# final_version.net
KiCad netlist of a schematic drawn in EAGLE
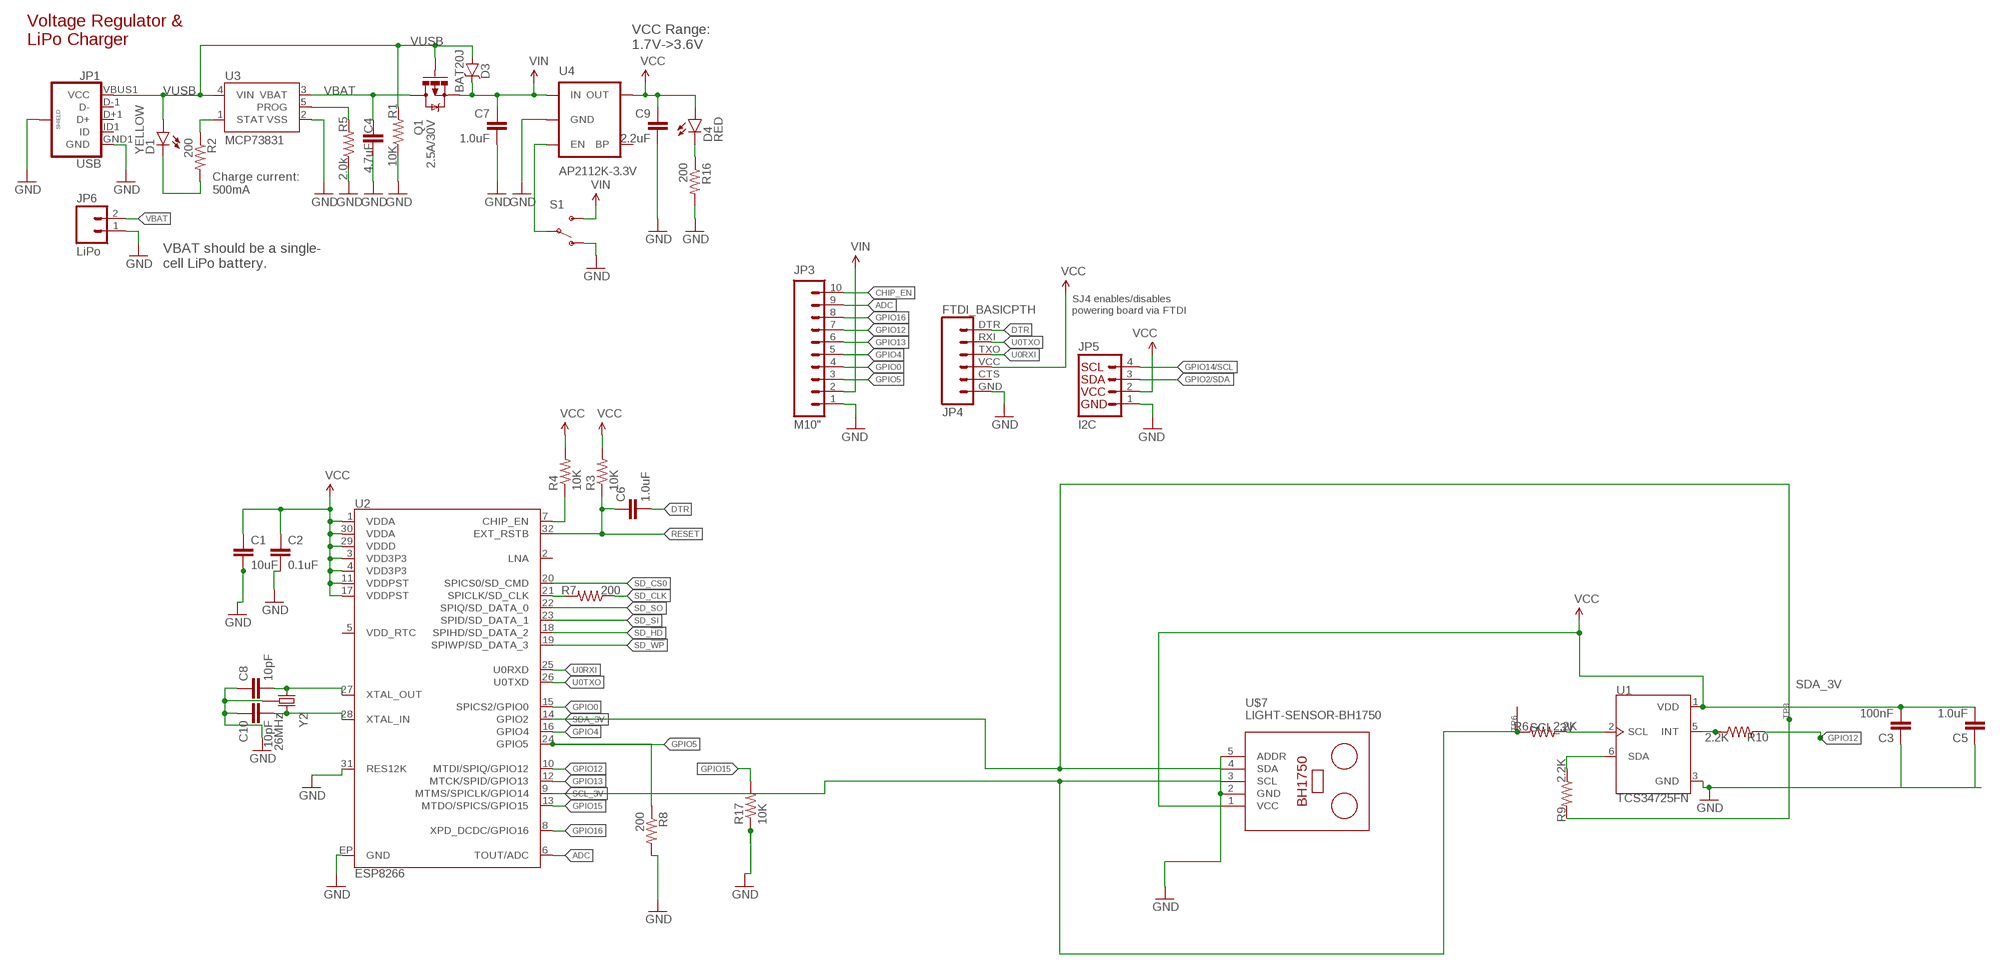
[diagram p0: schematic, sheet 1]

(export (version "E")
  (design (tool "Eeschema 10.0.6"))
  (components
    (comp (ref "C1")
      (value "10uF")
      (footprint "eagle-import:0603-CAP")
      (libsource (lib "eagle-import") (part "10UF-6.3V-20%(0603)"))
    )
    (comp (ref "C2")
      (value "0.1uF")
      (footprint "eagle-import:0603-CAP")
      (libsource (lib "eagle-import") (part "0.1UF-25V(+80/-20%)(0603)"))
    )
    (comp (ref "C3")
      (value "100nF")
      (footprint "eagle-import:0603-CAP")
      (libsource (lib "eagle-import") (part "1.0UF-16V-10%(0603)"))
    )
    (comp (ref "C4")
      (value "4.7uF")
      (footprint "eagle-import:0603-CAP")
      (libsource (lib "eagle-import") (part "4.7UF-6.3V-10%(0603)0603"))
    )
    (comp (ref "C5")
      (value "1.0uF")
      (footprint "eagle-import:0603-CAP")
      (libsource (lib "eagle-import") (part "1.0UF-16V-10%(0603)"))
    )
    (comp (ref "C6")
      (value "1.0uF")
      (footprint "eagle-import:0603-CAP")
      (libsource (lib "eagle-import") (part "1.0UF-16V-10%(0603)"))
    )
    (comp (ref "C7")
      (value "1.0uF")
      (footprint "eagle-import:0805")
      (libsource (lib "eagle-import") (part "1.0UF-25V-+80/-20(0805)"))
    )
    (comp (ref "C8")
      (value "10pF")
      (footprint "eagle-import:0603-CAP")
      (libsource (lib "eagle-import") (part "10PF-50V-5%(0603)"))
    )
    (comp (ref "C9")
      (value "2.2uF")
      (footprint "eagle-import:0603-CAP")
      (libsource (lib "eagle-import") (part "2.2UF-10V-20%(0603)"))
    )
    (comp (ref "C10")
      (value "10pF")
      (footprint "eagle-import:0603-CAP")
      (libsource (lib "eagle-import") (part "10PF-50V-5%(0603)"))
    )
    (comp (ref "D1")
      (value "YELLOW")
      (footprint "eagle-import:LED-0603")
      (libsource (lib "eagle-import") (part "LED-YELLOW0603"))
    )
    (comp (ref "D3")
      (value "BAT20J")
      (footprint "eagle-import:SOD-323")
      (libsource (lib "eagle-import") (part "DIODE-SCHOTTKY-BAT20J"))
    )
    (comp (ref "D4")
      (value "RED")
      (footprint "eagle-import:LED-0603")
      (libsource (lib "eagle-import") (part "LED-RED0603"))
    )
    (comp (ref "JP1")
      (value "USB")
      (footprint "eagle-import:USB-B-MICRO-SMD_V03")
      (libsource (lib "eagle-import") (part "USB_MICROB_PLUGCONN-11752"))
    )
    (comp (ref "JP3")
      (value "M10\"")
      (footprint "eagle-import:1X10")
      (libsource (lib "eagle-import") (part "M10{dblquote}"))
    )
    (comp (ref "JP4")
      (value "FTDI_BASICPTH")
      (footprint "eagle-import:FTDI_BASIC")
      (libsource (lib "eagle-import") (part "FTDI_BASICPTH"))
    )
    (comp (ref "JP5")
      (value "I2C")
      (footprint "eagle-import:1X04")
      (libsource (lib "eagle-import") (part "I2C_STANDARD"))
    )
    (comp (ref "JP6")
      (value "LiPo")
      (footprint "eagle-import:JST-2-PTH")
      (libsource (lib "eagle-import") (part "M02JST-PTH-2"))
    )
    (comp (ref "Q1")
      (value "2.5A/30V")
      (footprint "eagle-import:SOT23-3")
      (libsource (lib "eagle-import") (part "MOSFET-PCHANNELDMG2307L"))
    )
    (comp (ref "R1")
      (value "10K")
      (footprint "eagle-import:0603-RES")
      (libsource (lib "eagle-import") (part "10KOHM1/10W1%(0603)0603"))
    )
    (comp (ref "R2")
      (value "200")
      (footprint "eagle-import:0603-RES")
      (libsource (lib "eagle-import") (part "200OHM1/10W1%(0603)"))
    )
    (comp (ref "R3")
      (value "10K")
      (footprint "eagle-import:0603-RES")
      (libsource (lib "eagle-import") (part "10KOHM1/10W1%(0603)0603"))
    )
    (comp (ref "R4")
      (value "10K")
      (footprint "eagle-import:0603-RES")
      (libsource (lib "eagle-import") (part "10KOHM1/10W1%(0603)0603"))
    )
    (comp (ref "R5")
      (value "2.0k")
      (footprint "eagle-import:0603-RES")
      (libsource (lib "eagle-import") (part "2.0KOHM1/10W5%(0603)"))
    )
    (comp (ref "R6")
      (value "2.2K")
      (footprint "eagle-import:0603-RES")
      (libsource (lib "eagle-import") (part "200OHM1/10W1%(0603)"))
    )
    (comp (ref "R7")
      (value "200")
      (footprint "eagle-import:0603-RES")
      (libsource (lib "eagle-import") (part "200OHM1/10W1%(0603)"))
    )
    (comp (ref "R8")
      (value "200")
      (footprint "eagle-import:0603-RES")
      (libsource (lib "eagle-import") (part "200OHM1/10W1%(0603)"))
    )
    (comp (ref "R9")
      (value "2.2K")
      (footprint "eagle-import:0603-RES")
      (libsource (lib "eagle-import") (part "200OHM1/10W1%(0603)"))
    )
    (comp (ref "R10")
      (value "2.2K")
      (footprint "eagle-import:0603-RES")
      (libsource (lib "eagle-import") (part "200OHM1/10W1%(0603)"))
    )
    (comp (ref "R16")
      (value "200")
      (footprint "eagle-import:0603-RES")
      (libsource (lib "eagle-import") (part "200OHM1/10W1%(0603)"))
    )
    (comp (ref "R17")
      (value "10K")
      (footprint "eagle-import:0603-RES")
      (libsource (lib "eagle-import") (part "10KOHM1/10W1%(0603)0603"))
    )
    (comp (ref "S1")
      (value "SWITCH-SPDT-SMD-A")
      (footprint "eagle-import:SWITCH-SPST-SMD-A")
      (libsource (lib "eagle-import") (part "SWITCH-SPDT-SMD-A"))
    )
    (comp (ref "TP3")
      (value "SEWTAP0.5IN")
      (footprint "eagle-import:SEWINGTAP_0.5")
      (libsource (lib "eagle-import") (part "SEWTAP0.5IN"))
    )
    (comp (ref "TP6")
      (value "SEWTAP0.5IN")
      (footprint "eagle-import:SEWINGTAP_0.5")
      (libsource (lib "eagle-import") (part "SEWTAP0.5IN"))
    )
    (comp (ref "U$7")
      (value "LIGHT-SENSOR-BH1750")
      (footprint "eagle-import:LIGHT-SENSOR-BH1750")
      (libsource (lib "eagle-import") (part "LIGHT-SENSOR-BH1750"))
    )
    (comp (ref "U1")
      (value "TCS34725FN")
      (footprint "eagle-import:SON65P200X240X70-6N")
      (fields (field (name "DIGI-KEY_PART_NUMBER") "TCS34725FNCT-ND") (field (name "MF") "ams"))
      (libsource (lib "eagle-import") (part "TCS34725FN"))
    )
    (comp (ref "U2")
      (value "ESP8266")
      (footprint "eagle-import:QFN32")
      (libsource (lib "eagle-import") (part "ESP8266"))
    )
    (comp (ref "U3")
      (value "MCP73831")
      (footprint "eagle-import:SOT23-5")
      (libsource (lib "eagle-import") (part "MCP73831"))
    )
    (comp (ref "U4")
      (value "AP2112K-3.3V")
      (footprint "eagle-import:SOT23-5")
      (libsource (lib "eagle-import") (part "V_REG_LDOSMD"))
    )
    (comp (ref "Y2")
      (value "26MHz")
      (footprint "eagle-import:CRYSTAL-SMD-3.2X2.5")
      (libsource (lib "eagle-import") (part "CRYSTAL-GROUNDED3.2X2.5"))
    )
  )
  (nets
    (net (code "1") (name "/SD_~{HD}") (class "Default")
      (node (ref "U2") (pin "18") (pinfunction "SPIHD/SD_DATA_2_18") (pintype "bidirectional"))
    )
    (net (code "2") (name "/SD_~{WP}") (class "Default")
      (node (ref "U2") (pin "19") (pinfunction "SPIWP/SD_DATA_3_19") (pintype "bidirectional"))
    )
    (net (code "3") (name "/VUSB") (class "Default")
      (node (ref "D1") (pin "A") (pinfunction "A_A") (pintype "passive"))
      (node (ref "D3") (pin "A") (pinfunction "A_A") (pintype "passive"))
      (node (ref "JP1") (pin "VBUS1") (pinfunction "VCC_VBUS1") (pintype "bidirectional"))
      (node (ref "Q1") (pin "1") (pinfunction "G_1") (pintype "passive"))
      (node (ref "R1") (pin "2") (pinfunction "2_2") (pintype "passive"))
      (node (ref "U3") (pin "4") (pinfunction "VIN_4") (pintype "power_in"))
    )
    (net (code "4") (name "ADC") (class "Default")
      (node (ref "JP3") (pin "9") (pinfunction "9_9") (pintype "passive"))
      (node (ref "U2") (pin "6") (pinfunction "TOUT/ADC_6") (pintype "bidirectional"))
    )
    (net (code "5") (name "CHIP_EN") (class "Default")
      (node (ref "JP3") (pin "10") (pinfunction "10_10") (pintype "passive"))
      (node (ref "R4") (pin "1") (pinfunction "1_1") (pintype "passive"))
      (node (ref "U2") (pin "7") (pinfunction "CHIP_EN_7") (pintype "bidirectional"))
    )
    (net (code "6") (name "DTR") (class "Default")
      (node (ref "C6") (pin "2") (pinfunction "2_2") (pintype "passive"))
      (node (ref "JP4") (pin "DTR") (pinfunction "1_DTR") (pintype "passive"))
    )
    (net (code "7") (name "GND") (class "Default")
      (node (ref "C1") (pin "2") (pinfunction "2_2") (pintype "passive"))
      (node (ref "C10") (pin "1") (pinfunction "1_1") (pintype "passive"))
      (node (ref "C2") (pin "2") (pinfunction "2_2") (pintype "passive"))
      (node (ref "C3") (pin "1") (pinfunction "1_1") (pintype "passive"))
      (node (ref "C4") (pin "2") (pinfunction "2_2") (pintype "passive"))
      (node (ref "C5") (pin "1") (pinfunction "1_1") (pintype "passive"))
      (node (ref "C7") (pin "2") (pinfunction "2_2") (pintype "passive"))
      (node (ref "C8") (pin "1") (pinfunction "1_1") (pintype "passive"))
      (node (ref "C9") (pin "2") (pinfunction "2_2") (pintype "passive"))
      (node (ref "JP1") (pin "GND1") (pinfunction "GND_GND1") (pintype "bidirectional"))
      (node (ref "JP1") (pin "SHIELD1") (pinfunction "SHIELD_SHIELD1") (pintype "bidirectional"))
      (node (ref "JP1") (pin "SHIELD2") (pinfunction "SHIELD_SHIELD2") (pintype "bidirectional"))
      (node (ref "JP1") (pin "SHIELD3") (pinfunction "SHIELD_SHIELD3") (pintype "bidirectional"))
      (node (ref "JP3") (pin "1") (pinfunction "1_1") (pintype "passive"))
      (node (ref "JP4") (pin "GND") (pinfunction "6_GND") (pintype "passive"))
      (node (ref "JP5") (pin "1") (pinfunction "1_1") (pintype "passive"))
      (node (ref "JP6") (pin "1") (pinfunction "1_1") (pintype "passive"))
      (node (ref "R1") (pin "1") (pinfunction "1_1") (pintype "passive"))
      (node (ref "R16") (pin "2") (pinfunction "2_2") (pintype "passive"))
      (node (ref "R17") (pin "1") (pinfunction "1_1") (pintype "passive"))
      (node (ref "R5") (pin "1") (pinfunction "1_1") (pintype "passive"))
      (node (ref "R8") (pin "2") (pinfunction "2_2") (pintype "passive"))
      (node (ref "S1") (pin "1") (pinfunction "O_1") (pintype "passive"))
      (node (ref "U$7") (pin "2") (pinfunction "GND_2") (pintype "power_in"))
      (node (ref "U$7") (pin "5") (pinfunction "ADDR_5") (pintype "bidirectional"))
      (node (ref "U1") (pin "3") (pinfunction "GND_3") (pintype "power_in"))
      (node (ref "U2") (pin "31") (pinfunction "RES12K_31") (pintype "bidirectional"))
      (node (ref "U2") (pin "EP") (pinfunction "GND_EP") (pintype "bidirectional"))
      (node (ref "U3") (pin "2") (pinfunction "VSS_2") (pintype "power_in"))
      (node (ref "U4") (pin "2") (pinfunction "GND_2") (pintype "input"))
      (node (ref "Y2") (pin "2") (pinfunction "GND_2") (pintype "passive"))
      (node (ref "Y2") (pin "4") (pinfunction "GND_4") (pintype "passive"))
    )
    (net (code "8") (name "GPIO0") (class "Default")
      (node (ref "JP3") (pin "4") (pinfunction "4_4") (pintype "passive"))
      (node (ref "U2") (pin "15") (pinfunction "SPICS2/GPIO0_15") (pintype "bidirectional"))
    )
    (net (code "9") (name "GPIO2{slash}SDA") (class "Default")
      (node (ref "JP5") (pin "3") (pinfunction "3_3") (pintype "passive"))
    )
    (net (code "10") (name "GPIO4") (class "Default")
      (node (ref "JP3") (pin "5") (pinfunction "5_5") (pintype "passive"))
      (node (ref "U2") (pin "16") (pinfunction "GPIO4_16") (pintype "bidirectional"))
    )
    (net (code "11") (name "GPIO5") (class "Default")
      (node (ref "JP3") (pin "3") (pinfunction "3_3") (pintype "passive"))
      (node (ref "R8") (pin "1") (pinfunction "1_1") (pintype "passive"))
      (node (ref "U2") (pin "24") (pinfunction "GPIO5_24") (pintype "bidirectional"))
    )
    (net (code "12") (name "GPIO12") (class "Default")
      (node (ref "JP3") (pin "7") (pinfunction "7_7") (pintype "passive"))
      (node (ref "U2") (pin "10") (pinfunction "MTDI/SPIQ/GPIO12_10") (pintype "bidirectional"))
    )
    (net (code "13") (name "GPIO13") (class "Default")
      (node (ref "JP3") (pin "6") (pinfunction "6_6") (pintype "passive"))
      (node (ref "U2") (pin "12") (pinfunction "MTCK/SPID/GPIO13_12") (pintype "bidirectional"))
    )
    (net (code "14") (name "GPIO14{slash}SCL") (class "Default")
      (node (ref "JP5") (pin "4") (pinfunction "4_4") (pintype "passive"))
    )
    (net (code "15") (name "GPIO15") (class "Default")
      (node (ref "R17") (pin "2") (pinfunction "2_2") (pintype "passive"))
      (node (ref "U2") (pin "13") (pinfunction "MTDO/SPICS/GPIO15_13") (pintype "bidirectional"))
    )
    (net (code "16") (name "GPIO16") (class "Default")
      (node (ref "JP3") (pin "8") (pinfunction "8_8") (pintype "passive"))
      (node (ref "U2") (pin "8") (pinfunction "XPD_DCDC/GPIO16_8") (pintype "bidirectional"))
    )
    (net (code "17") (name "Net-(D1-PadC)") (class "Default")
      (node (ref "D1") (pin "C") (pinfunction "C_C") (pintype "passive"))
      (node (ref "R2") (pin "2") (pinfunction "2_2") (pintype "passive"))
    )
    (net (code "18") (name "Net-(D4-PadC)") (class "Default")
      (node (ref "D4") (pin "C") (pinfunction "C_C") (pintype "passive"))
      (node (ref "R16") (pin "1") (pinfunction "1_1") (pintype "passive"))
    )
    (net (code "19") (name "Net-(S1-P)") (class "Default")
      (node (ref "S1") (pin "2") (pinfunction "P_2") (pintype "passive"))
      (node (ref "U4") (pin "3") (pinfunction "EN_3") (pintype "input"))
    )
    (net (code "20") (name "Net-(U1-INT)") (class "Default")
      (node (ref "R10") (pin "1") (pinfunction "1_1") (pintype "passive"))
      (node (ref "U1") (pin "5") (pinfunction "INT_5") (pintype "output"))
    )
    (net (code "21") (name "Net-(U1-SCL)") (class "Default")
      (node (ref "R6") (pin "1") (pinfunction "1_1") (pintype "passive"))
      (node (ref "U1") (pin "2") (pinfunction "SCL_2") (pintype "input"))
    )
    (net (code "22") (name "Net-(U1-SDA)") (class "Default")
      (node (ref "R9") (pin "1") (pinfunction "1_1") (pintype "passive"))
      (node (ref "U1") (pin "6") (pinfunction "SDA_6") (pintype "bidirectional"))
    )
    (net (code "23") (name "Net-(U2-SPICLK{slash}SD_CLK)") (class "Default")
      (node (ref "R7") (pin "2") (pinfunction "2_2") (pintype "passive"))
      (node (ref "U2") (pin "21") (pinfunction "SPICLK/SD_CLK_21") (pintype "bidirectional"))
    )
    (net (code "24") (name "Net-(U2-XTAL_IN)") (class "Default")
      (node (ref "C10") (pin "2") (pinfunction "2_2") (pintype "passive"))
      (node (ref "U2") (pin "28") (pinfunction "XTAL_IN_28") (pintype "bidirectional"))
      (node (ref "Y2") (pin "3") (pinfunction "2_3") (pintype "passive"))
    )
    (net (code "25") (name "Net-(U2-XTAL_OUT)") (class "Default")
      (node (ref "C8") (pin "2") (pinfunction "2_2") (pintype "passive"))
      (node (ref "U2") (pin "27") (pinfunction "XTAL_OUT_27") (pintype "bidirectional"))
      (node (ref "Y2") (pin "1") (pinfunction "1_1") (pintype "passive"))
    )
    (net (code "26") (name "Net-(U3-PROG)") (class "Default")
      (node (ref "R5") (pin "2") (pinfunction "2_2") (pintype "passive"))
      (node (ref "U3") (pin "5") (pinfunction "PROG_5") (pintype "input"))
    )
    (net (code "27") (name "Net-(U3-STAT)") (class "Default")
      (node (ref "R2") (pin "1") (pinfunction "1_1") (pintype "passive"))
      (node (ref "U3") (pin "1") (pinfunction "STAT_1") (pintype "output"))
    )
    (net (code "28") (name "RESET") (class "Default")
      (node (ref "C6") (pin "1") (pinfunction "1_1") (pintype "passive"))
      (node (ref "R3") (pin "1") (pinfunction "1_1") (pintype "passive"))
      (node (ref "U2") (pin "32") (pinfunction "EXT_RSTB_32") (pintype "bidirectional"))
    )
    (net (code "29") (name "SCL_3V") (class "Default")
      (node (ref "R6") (pin "2") (pinfunction "2_2") (pintype "passive"))
      (node (ref "TP6") (pin "TAP") (pinfunction "SEW_TAP") (pintype "bidirectional"))
      (node (ref "U$7") (pin "3") (pinfunction "SCL_3") (pintype "bidirectional"))
      (node (ref "U2") (pin "9") (pinfunction "MTMS/SPICLK/GPIO14_9") (pintype "bidirectional"))
    )
    (net (code "30") (name "SDA_3V") (class "Default")
      (node (ref "R9") (pin "2") (pinfunction "2_2") (pintype "passive"))
      (node (ref "TP3") (pin "TAP") (pinfunction "SEW_TAP") (pintype "bidirectional"))
      (node (ref "U$7") (pin "4") (pinfunction "SDA_4") (pintype "bidirectional"))
      (node (ref "U2") (pin "14") (pinfunction "GPIO2_14") (pintype "bidirectional"))
    )
    (net (code "31") (name "SD_CLK") (class "Default")
      (node (ref "R7") (pin "1") (pinfunction "1_1") (pintype "passive"))
    )
    (net (code "32") (name "SD_CS0") (class "Default")
      (node (ref "U2") (pin "20") (pinfunction "SPICS0/SD_CMD_20") (pintype "bidirectional"))
    )
    (net (code "33") (name "SD_SI") (class "Default")
      (node (ref "U2") (pin "23") (pinfunction "SPID/SD_DATA_1_23") (pintype "bidirectional"))
    )
    (net (code "34") (name "SD_SO") (class "Default")
      (node (ref "U2") (pin "22") (pinfunction "SPIQ/SD_DATA_0_22") (pintype "bidirectional"))
    )
    (net (code "35") (name "U0RXI") (class "Default")
      (node (ref "JP4") (pin "TXO") (pinfunction "3_TXO") (pintype "passive"))
      (node (ref "U2") (pin "25") (pinfunction "U0RXD_25") (pintype "bidirectional"))
    )
    (net (code "36") (name "U0TXO") (class "Default")
      (node (ref "JP4") (pin "RXI") (pinfunction "2_RXI") (pintype "passive"))
      (node (ref "U2") (pin "26") (pinfunction "U0TXD_26") (pintype "bidirectional"))
    )
    (net (code "37") (name "VBAT") (class "Default")
      (node (ref "C4") (pin "1") (pinfunction "1_1") (pintype "passive"))
      (node (ref "JP6") (pin "2") (pinfunction "2_2") (pintype "passive"))
      (node (ref "Q1") (pin "3") (pinfunction "D_3") (pintype "passive"))
      (node (ref "U3") (pin "3") (pinfunction "VBAT_3") (pintype "power_in"))
    )
    (net (code "38") (name "VCC") (class "Default")
      (node (ref "C1") (pin "1") (pinfunction "1_1") (pintype "passive"))
      (node (ref "C2") (pin "1") (pinfunction "1_1") (pintype "passive"))
      (node (ref "C3") (pin "2") (pinfunction "2_2") (pintype "passive"))
      (node (ref "C5") (pin "2") (pinfunction "2_2") (pintype "passive"))
      (node (ref "C9") (pin "1") (pinfunction "1_1") (pintype "passive"))
      (node (ref "D4") (pin "A") (pinfunction "A_A") (pintype "passive"))
      (node (ref "JP4") (pin "VCC") (pinfunction "4_VCC") (pintype "passive"))
      (node (ref "JP5") (pin "2") (pinfunction "2_2") (pintype "passive"))
      (node (ref "R3") (pin "2") (pinfunction "2_2") (pintype "passive"))
      (node (ref "R4") (pin "2") (pinfunction "2_2") (pintype "passive"))
      (node (ref "U$7") (pin "1") (pinfunction "VCC_1") (pintype "power_in"))
      (node (ref "U1") (pin "1") (pinfunction "VDD_1") (pintype "power_in"))
      (node (ref "U2") (pin "1") (pinfunction "VDDA_1") (pintype "bidirectional"))
      (node (ref "U2") (pin "11") (pinfunction "VDDPST_11") (pintype "bidirectional"))
      (node (ref "U2") (pin "17") (pinfunction "VDDPST_17") (pintype "bidirectional"))
      (node (ref "U2") (pin "29") (pinfunction "VDDD_29") (pintype "bidirectional"))
      (node (ref "U2") (pin "3") (pinfunction "VDD3P3_3") (pintype "bidirectional"))
      (node (ref "U2") (pin "30") (pinfunction "VDDA_30") (pintype "bidirectional"))
      (node (ref "U2") (pin "4") (pinfunction "VDD3P3_4") (pintype "bidirectional"))
      (node (ref "U4") (pin "5") (pinfunction "OUT_5") (pintype "passive"))
    )
    (net (code "39") (name "VIN") (class "Default")
      (node (ref "C7") (pin "1") (pinfunction "1_1") (pintype "passive"))
      (node (ref "D3") (pin "C") (pinfunction "C_C") (pintype "passive"))
      (node (ref "JP3") (pin "2") (pinfunction "2_2") (pintype "passive"))
      (node (ref "Q1") (pin "2") (pinfunction "S_2") (pintype "passive"))
      (node (ref "S1") (pin "3") (pinfunction "S_3") (pintype "passive"))
      (node (ref "U4") (pin "1") (pinfunction "IN_1") (pintype "input"))
    )
    (net (code "40") (name "unconnected-(JP1-D+-PadD+1)") (class "Default")
      (node (ref "JP1") (pin "D+1") (pinfunction "D+_D+1") (pintype "bidirectional"))
    )
    (net (code "41") (name "unconnected-(JP1-D--PadD-1)") (class "Default")
      (node (ref "JP1") (pin "D-1") (pinfunction "D-_D-1") (pintype "bidirectional"))
    )
    (net (code "42") (name "unconnected-(JP1-ID-PadID1)") (class "Default")
      (node (ref "JP1") (pin "ID1") (pinfunction "ID_ID1") (pintype "bidirectional"))
    )
    (net (code "43") (name "unconnected-(JP4-5-PadCTS)") (class "Default")
      (node (ref "JP4") (pin "CTS") (pinfunction "5_CTS") (pintype "passive"))
    )
    (net (code "44") (name "unconnected-(R10-Pad2)") (class "Default")
      (node (ref "R10") (pin "2") (pinfunction "2_2") (pintype "passive"))
    )
    (net (code "45") (name "unconnected-(U2-LNA-Pad2)") (class "Default")
      (node (ref "U2") (pin "2") (pinfunction "LNA_2") (pintype "bidirectional"))
    )
    (net (code "46") (name "unconnected-(U2-VDD_RTC-Pad5)") (class "Default")
      (node (ref "U2") (pin "5") (pinfunction "VDD_RTC_5") (pintype "bidirectional"))
    )
    (net (code "47") (name "unconnected-(U4-BP-Pad4)") (class "Default")
      (node (ref "U4") (pin "4") (pinfunction "BP_4") (pintype "input"))
    )
  )
)
